# LARIX_V5_1.net
KiCad netlist of a schematic drawn in Altium Designer
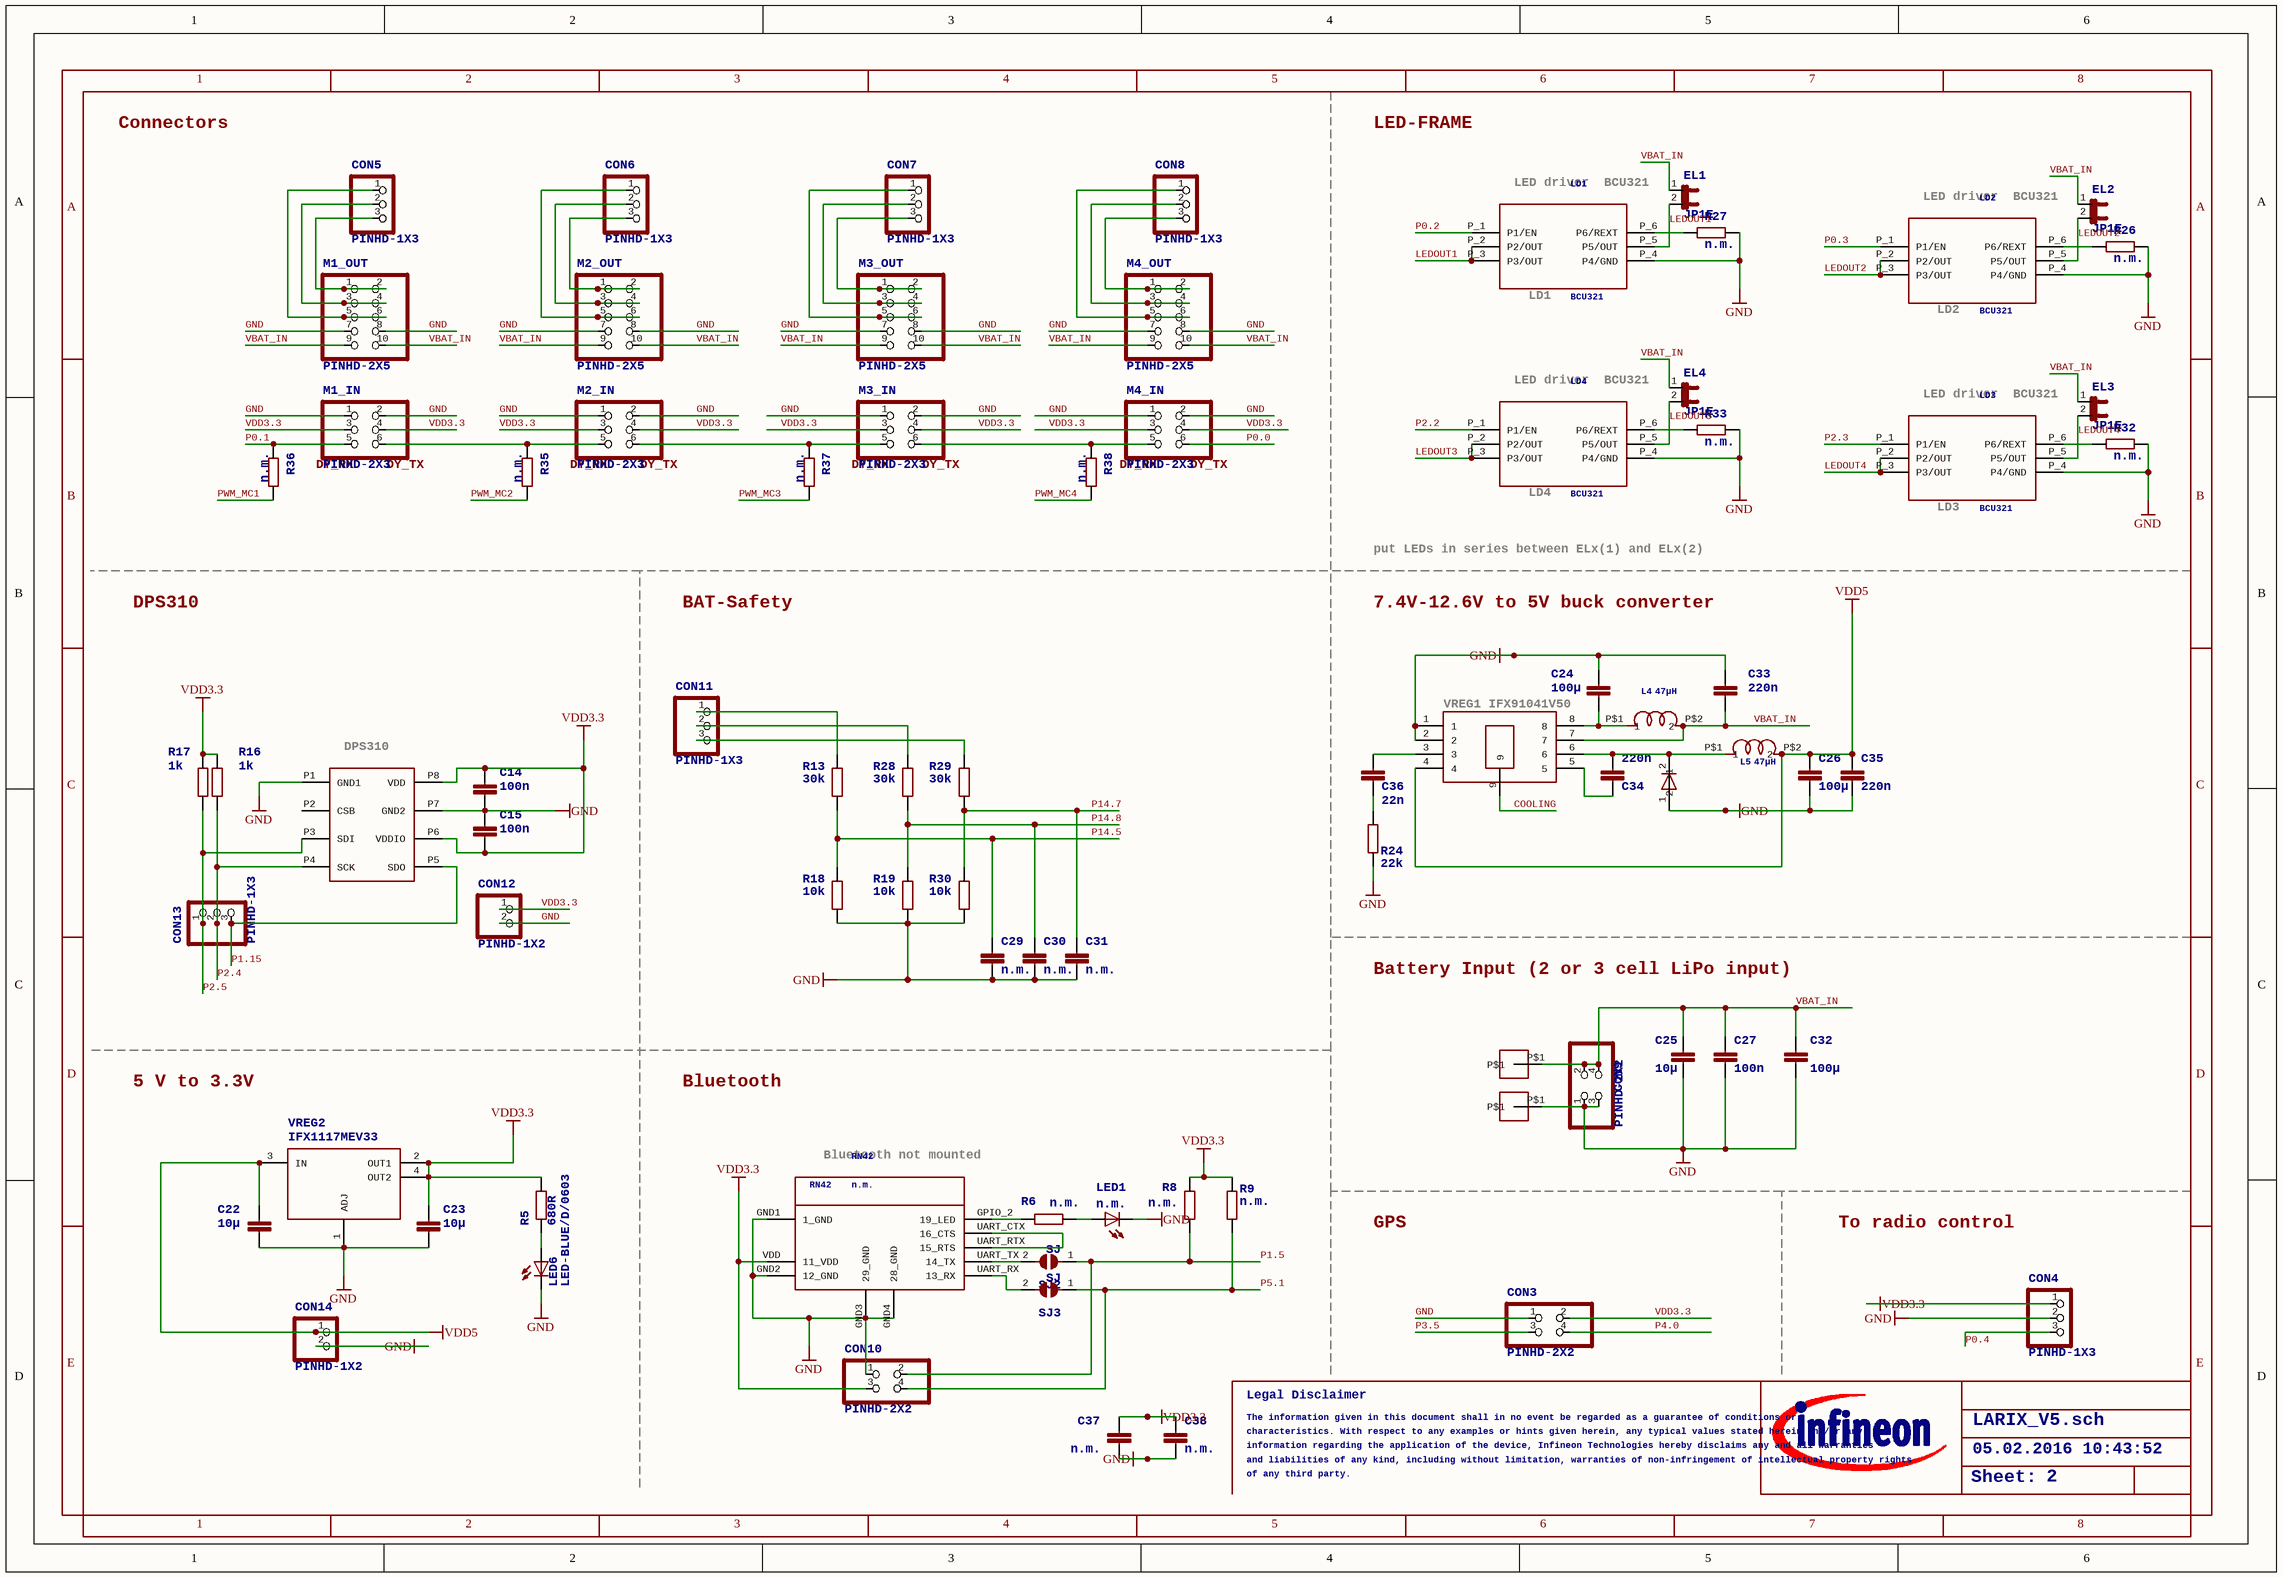
[diagram p0: LARIX_V5_1.SchDoc]

(export (version "E")
  (design (tool "Eeschema 10.0.6"))
  (components
    (comp (ref "C14")
      (value "100n")
      (footprint "C0603")
      (description "<B>CAPACITOR</B>, European symbol")
      (libsource (lib "libresistor") (part "C-EUC0603"))
    )
    (comp (ref "C15")
      (value "100n")
      (footprint "C0603")
      (description "<B>CAPACITOR</B>, European symbol")
      (libsource (lib "libresistor") (part "C-EUC0603"))
    )
    (comp (ref "C22")
      (value "10µ")
      (footprint "C0805K")
      (description "<B>CAPACITOR</B>, European symbol")
      (libsource (lib "libHMI_OLED-V1") (part "C-EUC0805K"))
    )
    (comp (ref "C23")
      (value "10µ")
      (footprint "C0805K")
      (description "<B>CAPACITOR</B>, European symbol")
      (libsource (lib "libHMI_OLED-V1") (part "C-EUC0805K"))
    )
    (comp (ref "C24")
      (value "100µ")
      (footprint "C1210")
      (description "<B>CAPACITOR</B>, European symbol")
      (libsource (lib "libresistor") (part "C-EUC1210"))
    )
    (comp (ref "C25")
      (value "10µ")
      (footprint "C0805K")
      (description "<B>CAPACITOR</B>, European symbol")
      (libsource (lib "libHMI_OLED-V1") (part "C-EUC0805K"))
    )
    (comp (ref "C26")
      (value "100µ")
      (footprint "C1210")
      (description "<B>CAPACITOR</B>, European symbol")
      (fields (field (name ">NAME") "C26") (field (name ">VALUE") "100µ"))
      (libsource (lib "libresistor") (part "C-EUC1210"))
    )
    (comp (ref "C27")
      (value "100n")
      (footprint "C0603")
      (description "<B>CAPACITOR</B>, European symbol")
      (libsource (lib "libresistor") (part "C-EUC0603"))
    )
    (comp (ref "C29")
      (value "n.m.")
      (footprint "C0603")
      (description "<B>CAPACITOR</B>, European symbol")
      (libsource (lib "libresistor") (part "C-EUC0603"))
    )
    (comp (ref "C30")
      (value "n.m.")
      (footprint "C0603")
      (description "<B>CAPACITOR</B>, European symbol")
      (libsource (lib "libresistor") (part "C-EUC0603"))
    )
    (comp (ref "C31")
      (value "n.m.")
      (footprint "C0603")
      (description "<B>CAPACITOR</B>, European symbol")
      (libsource (lib "libresistor") (part "C-EUC0603"))
    )
    (comp (ref "C32")
      (value "100µ")
      (footprint "C1210")
      (description "<B>CAPACITOR</B>, European symbol")
      (libsource (lib "libresistor") (part "C-EUC1210"))
    )
    (comp (ref "C33")
      (value "220n")
      (footprint "C0603")
      (description "<B>CAPACITOR</B>, European symbol")
      (libsource (lib "libresistor") (part "C-EUC0603"))
    )
    (comp (ref "C34")
      (value "220n")
      (footprint "C0603")
      (description "<B>CAPACITOR</B>, European symbol")
      (libsource (lib "libresistor") (part "C-EUC0603"))
    )
    (comp (ref "C35")
      (value "220n")
      (footprint "C0603")
      (description "<B>CAPACITOR</B>, European symbol")
      (libsource (lib "libresistor") (part "C-EUC0603"))
    )
    (comp (ref "C36")
      (value "22n")
      (footprint "C0603")
      (description "<B>CAPACITOR</B>, European symbol")
      (libsource (lib "libresistor") (part "C-EUC0603"))
    )
    (comp (ref "C37")
      (value "n.m.")
      (footprint "C0805K")
      (description "<B>CAPACITOR</B>, European symbol")
      (libsource (lib "libHMI_OLED-V1") (part "C-EUC0805K"))
    )
    (comp (ref "C38")
      (value "n.m.")
      (footprint "C0603")
      (description "<B>CAPACITOR</B>, European symbol")
      (libsource (lib "libresistor") (part "C-EUC0603"))
    )
    (comp (ref "CON3")
      (value "PINHD-2X2")
      (footprint "2X02")
      (description "<b>PIN HEADER</b>")
      (fields (field (name ">NAME") "CON3") (field (name ">VALUE") "PINHD-2X2"))
      (libsource (lib "pinhead") (part "PINHD-2X2"))
    )
    (comp (ref "CON4")
      (value "PINHD-1X3")
      (footprint "1X03")
      (description "<b>PIN HEADER</b>")
      (fields (field (name ">NAME") "CON4") (field (name ">VALUE") "PINHD-1X3"))
      (libsource (lib "pinhead") (part "PINHD-1X3"))
    )
    (comp (ref "CON5")
      (value "PINHD-1X3")
      (footprint "1X03")
      (description "<b>PIN HEADER</b>")
      (fields (field (name ">NAME") "CON5") (field (name ">VALUE") "PINHD-1X3"))
      (libsource (lib "pinhead") (part "PINHD-1X3"))
    )
    (comp (ref "CON6")
      (value "PINHD-1X3")
      (footprint "1X03")
      (description "<b>PIN HEADER</b>")
      (fields (field (name ">NAME") "CON6") (field (name ">VALUE") "PINHD-1X3"))
      (libsource (lib "pinhead") (part "PINHD-1X3"))
    )
    (comp (ref "CON7")
      (value "PINHD-1X3")
      (footprint "1X03")
      (description "<b>PIN HEADER</b>")
      (fields (field (name ">NAME") "CON7") (field (name ">VALUE") "PINHD-1X3"))
      (libsource (lib "pinhead") (part "PINHD-1X3"))
    )
    (comp (ref "CON8")
      (value "PINHD-1X3")
      (footprint "1X03")
      (description "<b>PIN HEADER</b>")
      (fields (field (name ">NAME") "CON8") (field (name ">VALUE") "PINHD-1X3"))
      (libsource (lib "pinhead") (part "PINHD-1X3"))
    )
    (comp (ref "CON9")
      (value "PINHD-2X2")
      (footprint "2X02")
      (description "<b>PIN HEADER</b>")
      (libsource (lib "pinhead") (part "PINHD-2X2"))
    )
    (comp (ref "CON10")
      (value "PINHD-2X2")
      (footprint "2X02")
      (description "<b>PIN HEADER</b>")
      (fields (field (name ">NAME") "CON10") (field (name ">VALUE") "PINHD-2X2"))
      (libsource (lib "pinhead") (part "PINHD-2X2"))
    )
    (comp (ref "CON11")
      (value "PINHD-1X3")
      (footprint "1X03")
      (description "<b>PIN HEADER</b>")
      (fields (field (name ">NAME") "CON11") (field (name ">VALUE") "PINHD-1X3"))
      (libsource (lib "pinhead") (part "PINHD-1X3"))
    )
    (comp (ref "CON12")
      (value "PINHD-1X2")
      (footprint "1X02")
      (description "<b>PIN HEADER</b>")
      (fields (field (name ">NAME") "CON12") (field (name ">VALUE") "PINHD-1X2"))
      (libsource (lib "pinhead") (part "PINHD-1X2"))
    )
    (comp (ref "CON13")
      (value "PINHD-1X3")
      (footprint "1X03")
      (description "<b>PIN HEADER</b>")
      (fields (field (name ">NAME") "CON13") (field (name ">VALUE") "PINHD-1X3"))
      (libsource (lib "pinhead") (part "PINHD-1X3"))
    )
    (comp (ref "CON14")
      (value "PINHD-1X2")
      (footprint "1X02")
      (description "<b>PIN HEADER</b>")
      (fields (field (name ">NAME") "CON14") (field (name ">VALUE") "PINHD-1X2"))
      (libsource (lib "pinhead") (part "PINHD-1X2"))
    )
    (comp (ref "D6")
      (value "BAS21-03W")
      (footprint "INF-SOD323_V_1PRIMARY")
      (libsource (lib "libBAS21-03W_INF-SOD323V") (part "INF-SOD323_V_1"))
    )
    (comp (ref "DPS310")
      (value "Infineon")
      (footprint "LGA8R125P0X4_500X300X120")
      (libsource (lib "libdrucksensorDPS310") (part "DPS310DRUCKSENSOR"))
    )
    (comp (ref "EL1")
      (value "JP1E")
      (footprint "JP1")
      (description "<b>JUMPER</b>")
      (fields (field (name ">NAME") "EL1") (field (name ">VALUE") "JP1E"))
      (libsource (lib "libjumper") (part "JP1E"))
    )
    (comp (ref "EL2")
      (value "JP1E")
      (footprint "JP1")
      (description "<b>JUMPER</b>")
      (fields (field (name ">NAME") "EL2") (field (name ">VALUE") "JP1E"))
      (libsource (lib "libjumper") (part "JP1E"))
    )
    (comp (ref "EL3")
      (value "JP1E")
      (footprint "JP1")
      (description "<b>JUMPER</b>")
      (fields (field (name ">NAME") "EL3") (field (name ">VALUE") "JP1E"))
      (libsource (lib "libjumper") (part "JP1E"))
    )
    (comp (ref "EL4")
      (value "JP1E")
      (footprint "JP1")
      (description "<b>JUMPER</b>")
      (fields (field (name ">NAME") "EL4") (field (name ">VALUE") "JP1E"))
      (libsource (lib "libjumper") (part "JP1E"))
    )
    (comp (ref "L4")
      (value "47µH")
      (footprint "WE-TPC")
      (libsource (lib "lib47µHWuerthChoke") (part "WUERTH47UHIND"))
    )
    (comp (ref "L5")
      (value "47µH")
      (footprint "WE-TPC")
      (libsource (lib "lib47µHWuerthChoke") (part "WUERTH47UHIND"))
    )
    (comp (ref "LD1")
      (value "BCU321")
      (footprint "SC74")
      (fields (field (name ">NAME") "LD1") (field (name ">VALUE") "BCU321"))
      (libsource (lib "libLEDtreiber BCR320U") (part "BCU320"))
    )
    (comp (ref "LD2")
      (value "BCU321")
      (footprint "SC74")
      (fields (field (name ">NAME") "LD2") (field (name ">VALUE") "BCU321"))
      (libsource (lib "libLEDtreiber BCR320U") (part "BCU320"))
    )
    (comp (ref "LD3")
      (value "BCU321")
      (footprint "SC74")
      (fields (field (name ">NAME") "LD3") (field (name ">VALUE") "BCU321"))
      (libsource (lib "libLEDtreiber BCR320U") (part "BCU320"))
    )
    (comp (ref "LD4")
      (value "BCU321")
      (footprint "SC74")
      (fields (field (name ">NAME") "LD4") (field (name ">VALUE") "BCU321"))
      (libsource (lib "libLEDtreiber BCR320U") (part "BCU320"))
    )
    (comp (ref "LED1")
      (value "n.m.")
      (footprint "CHIPLED_0603")
      (libsource (lib "libled") (part "LEDCHIPLED_0603"))
    )
    (comp (ref "LED6")
      (value "LED-BLUE/D/0603")
      (footprint "CHIPLED_0603")
      (fields (field (name ">NAME") "LED6") (field (name ">VALUE") "LED-BLUE/D/0603"))
      (libsource (lib "libled") (part "LEDCHIPLED_0603"))
    )
    (comp (ref "M1_IN")
      (value "PINHD-2X3")
      (footprint "2X03")
      (description "<b>PIN HEADER</b>")
      (fields (field (name ">NAME") "M1_IN") (field (name ">VALUE") "PINHD-2X3"))
      (libsource (lib "pinhead") (part "PINHD-2X3"))
    )
    (comp (ref "M1_OUT")
      (value "PINHD-2X5")
      (footprint "2X05")
      (description "<b>PIN HEADER</b>")
      (fields (field (name ">NAME") "M1_OUT") (field (name ">VALUE") "PINHD-2X5"))
      (libsource (lib "pinhead") (part "PINHD-2X5"))
    )
    (comp (ref "M2_IN")
      (value "PINHD-2X3")
      (footprint "2X03")
      (description "<b>PIN HEADER</b>")
      (fields (field (name ">NAME") "M2_IN") (field (name ">VALUE") "PINHD-2X3"))
      (libsource (lib "pinhead") (part "PINHD-2X3"))
    )
    (comp (ref "M2_OUT")
      (value "PINHD-2X5")
      (footprint "2X05")
      (description "<b>PIN HEADER</b>")
      (fields (field (name ">NAME") "M2_OUT") (field (name ">VALUE") "PINHD-2X5"))
      (libsource (lib "pinhead") (part "PINHD-2X5"))
    )
    (comp (ref "M3_IN")
      (value "PINHD-2X3")
      (footprint "2X03")
      (description "<b>PIN HEADER</b>")
      (fields (field (name ">NAME") "M3_IN") (field (name ">VALUE") "PINHD-2X3"))
      (libsource (lib "pinhead") (part "PINHD-2X3"))
    )
    (comp (ref "M3_OUT")
      (value "PINHD-2X5")
      (footprint "2X05")
      (description "<b>PIN HEADER</b>")
      (fields (field (name ">NAME") "M3_OUT") (field (name ">VALUE") "PINHD-2X5"))
      (libsource (lib "pinhead") (part "PINHD-2X5"))
    )
    (comp (ref "M4_IN")
      (value "PINHD-2X3")
      (footprint "2X03")
      (description "<b>PIN HEADER</b>")
      (fields (field (name ">NAME") "M4_IN") (field (name ">VALUE") "PINHD-2X3"))
      (libsource (lib "pinhead") (part "PINHD-2X3"))
    )
    (comp (ref "M4_OUT")
      (value "PINHD-2X5")
      (footprint "2X05")
      (description "<b>PIN HEADER</b>")
      (fields (field (name ">NAME") "M4_OUT") (field (name ">VALUE") "PINHD-2X5"))
      (libsource (lib "pinhead") (part "PINHD-2X5"))
    )
    (comp (ref "PAD1")
      (value "PAD-BATTERY")
      (footprint "BATT-SOLDER")
      (libsource (lib "pad_battery") (part "PAD-BATTERY"))
    )
    (comp (ref "PAD2")
      (value "PAD-BATTERY")
      (footprint "BATT-SOLDER")
      (libsource (lib "pad_battery") (part "PAD-BATTERY"))
    )
    (comp (ref "R5")
      (value "680R")
      (footprint "R0603")
      (fields (field (name ">NAME") "R5") (field (name ">VALUE") "680R"))
      (libsource (lib "libDsR") (part "R-EU_R0603"))
    )
    (comp (ref "R6") (value "n.m.") (footprint "R0603") (libsource (lib "libDsR") (part "R-EU_R0603")))
    (comp (ref "R8") (value "n.m.") (footprint "R0603") (libsource (lib "libDsR") (part "R-EU_R0603")))
    (comp (ref "R9") (value "n.m.") (footprint "R0603") (libsource (lib "libDsR") (part "R-EU_R0603")))
    (comp (ref "R13") (value "30k") (footprint "R0603") (libsource (lib "libDsR") (part "R-EU_R0603")))
    (comp (ref "R16") (value "1k") (footprint "R0603") (libsource (lib "libDsR") (part "R-EU_R0603")))
    (comp (ref "R17") (value "1k") (footprint "R0603") (libsource (lib "libDsR") (part "R-EU_R0603")))
    (comp (ref "R18") (value "10k") (footprint "R0603") (libsource (lib "libDsR") (part "R-EU_R0603")))
    (comp (ref "R19") (value "10k") (footprint "R0603") (libsource (lib "libDsR") (part "R-EU_R0603")))
    (comp (ref "R24") (value "22k") (footprint "R0603") (libsource (lib "libDsR") (part "R-EU_R0603")))
    (comp (ref "R26")
      (value "n.m.")
      (footprint "R0603")
      (description "<B>RESISTOR</B>, European symbol")
      (libsource (lib "libresistor") (part "R-EU_R0603"))
    )
    (comp (ref "R27")
      (value "n.m.")
      (footprint "R0603")
      (description "<B>RESISTOR</B>, European symbol")
      (libsource (lib "libresistor") (part "R-EU_R0603"))
    )
    (comp (ref "R28") (value "30k") (footprint "R0603") (libsource (lib "libDsR") (part "R-EU_R0603")))
    (comp (ref "R29") (value "30k") (footprint "R0603") (libsource (lib "libDsR") (part "R-EU_R0603")))
    (comp (ref "R30") (value "10k") (footprint "R0603") (libsource (lib "libDsR") (part "R-EU_R0603")))
    (comp (ref "R32")
      (value "n.m.")
      (footprint "R0603")
      (description "<B>RESISTOR</B>, European symbol")
      (libsource (lib "libresistor") (part "R-EU_R0603"))
    )
    (comp (ref "R33")
      (value "n.m.")
      (footprint "R0603")
      (description "<B>RESISTOR</B>, European symbol")
      (libsource (lib "libresistor") (part "R-EU_R0603"))
    )
    (comp (ref "R35")
      (value "n.m.")
      (footprint "R0603")
      (description "<B>RESISTOR</B>, European symbol")
      (fields (field (name ">NAME") "R35") (field (name ">VALUE") "n.m."))
      (libsource (lib "libresistor") (part "R-EU_R0603"))
    )
    (comp (ref "R36")
      (value "n.m.")
      (footprint "R0603")
      (description "<B>RESISTOR</B>, European symbol")
      (fields (field (name ">NAME") "R36") (field (name ">VALUE") "n.m."))
      (libsource (lib "libresistor") (part "R-EU_R0603"))
    )
    (comp (ref "R37")
      (value "n.m.")
      (footprint "R0603")
      (fields (field (name ">NAME") "R37") (field (name ">VALUE") "n.m."))
      (libsource (lib "libDsR") (part "R-EU_R0603"))
    )
    (comp (ref "R38")
      (value "n.m.")
      (footprint "R0603")
      (description "<B>RESISTOR</B>, European symbol")
      (fields (field (name ">NAME") "R38") (field (name ">VALUE") "n.m."))
      (libsource (lib "libresistor") (part "R-EU_R0603"))
    )
    (comp (ref "RN42")
      (value "n.m.")
      (footprint "RN42+SHIELD")
      (fields (field (name "RN42") "RN42") (field (name ">NAME") "RN42") (field (name ">VALUE") "n.m."))
      (libsource (lib "libbluetoothRN42") (part "BLUETOOTHRN42+SHIELD"))
    )
    (comp (ref "SJ2")
      (value "SJ")
      (footprint "SJ")
      (description "SMD solder <b>JUMPER</b>")
      (fields (field (name ">NAME") "SJ2") (field (name ">VALUE") "SJ"))
      (libsource (lib "jumper") (part "SJ"))
    )
    (comp (ref "SJ3")
      (value "SJ")
      (footprint "SJ")
      (description "SMD solder <b>JUMPER</b>")
      (fields (field (name ">NAME") "SJ3") (field (name ">VALUE") "SJ"))
      (libsource (lib "jumper") (part "SJ"))
    )
    (comp (ref "VREG1")
      (value "IFX91041V50")
      (footprint "INF-PG-DSO-8-27_N_1PRIMARY")
      (libsource (lib "libInfineon-DCDC-91041 - DSO-8") (part "INF-PG-DSO-8-27_N_1"))
    )
    (comp (ref "VREG2")
      (value "IFX1117MEV33")
      (footprint "SOT223")
      (fields (field (name ">NAME") "VREG2") (field (name ">VALUE") "IFX1117MEV33"))
      (libsource (lib "libXMC4500_Relax-V1+USBvertical") (part "IFX1117"))
    )
  )
  (nets
    (net (code "1") (name "/COOLING") (class "Default")
      (node (ref "VREG1") (pin "9") (pinfunction "9_9") (pintype "passive"))
    )
    (net (code "2") (name "/LEDOUT1") (class "Default")
      (node (ref "EL1") (pin "2") (pinfunction "2_2") (pintype "passive"))
      (node (ref "LD1") (pin "P_2") (pinfunction "P2/OUT_P_2") (pintype "passive"))
      (node (ref "LD1") (pin "P_3") (pinfunction "P3/OUT_P_3") (pintype "passive"))
      (node (ref "LD1") (pin "P_5") (pinfunction "P5/OUT_P_5") (pintype "passive"))
    )
    (net (code "3") (name "/LEDOUT2") (class "Default")
      (node (ref "EL2") (pin "2") (pinfunction "2_2") (pintype "passive"))
      (node (ref "LD2") (pin "P_2") (pinfunction "P2/OUT_P_2") (pintype "passive"))
      (node (ref "LD2") (pin "P_3") (pinfunction "P3/OUT_P_3") (pintype "passive"))
      (node (ref "LD2") (pin "P_5") (pinfunction "P5/OUT_P_5") (pintype "passive"))
    )
    (net (code "4") (name "/LEDOUT3") (class "Default")
      (node (ref "EL4") (pin "2") (pinfunction "2_2") (pintype "passive"))
      (node (ref "LD4") (pin "P_2") (pinfunction "P2/OUT_P_2") (pintype "passive"))
      (node (ref "LD4") (pin "P_3") (pinfunction "P3/OUT_P_3") (pintype "passive"))
      (node (ref "LD4") (pin "P_5") (pinfunction "P5/OUT_P_5") (pintype "passive"))
    )
    (net (code "5") (name "/LEDOUT4") (class "Default")
      (node (ref "EL3") (pin "2") (pinfunction "2_2") (pintype "passive"))
      (node (ref "LD3") (pin "P_2") (pinfunction "P2/OUT_P_2") (pintype "passive"))
      (node (ref "LD3") (pin "P_3") (pinfunction "P3/OUT_P_3") (pintype "passive"))
      (node (ref "LD3") (pin "P_5") (pinfunction "P5/OUT_P_5") (pintype "passive"))
    )
    (net (code "6") (name "/P0.0") (class "Default")
      (node (ref "M4_IN") (pin "6") (pinfunction "6_6") (pintype "passive"))
    )
    (net (code "7") (name "/P0.1") (class "Default")
      (node (ref "M1_IN") (pin "5") (pinfunction "5_5") (pintype "passive"))
      (node (ref "R36") (pin "1") (pinfunction "1_1") (pintype "passive"))
    )
    (net (code "8") (name "/P0.2") (class "Default")
      (node (ref "LD1") (pin "P_1") (pinfunction "P1/EN_P_1") (pintype "passive"))
    )
    (net (code "9") (name "/P0.3") (class "Default")
      (node (ref "LD2") (pin "P_1") (pinfunction "P1/EN_P_1") (pintype "passive"))
    )
    (net (code "10") (name "/P0.4") (class "Default")
      (node (ref "CON4") (pin "3") (pinfunction "3_3") (pintype "passive"))
    )
    (net (code "11") (name "/P1.5") (class "Default")
      (node (ref "CON10") (pin "2") (pinfunction "2_2") (pintype "passive"))
      (node (ref "R8") (pin "2") (pinfunction "2_2") (pintype "passive"))
      (node (ref "SJ2") (pin "1") (pinfunction "1_1") (pintype "passive"))
    )
    (net (code "12") (name "/P1.15") (class "Default")
      (node (ref "CON13") (pin "3") (pinfunction "3_3") (pintype "passive"))
      (node (ref "DPS310") (pin "P5") (pinfunction "SDO_P5") (pintype "passive"))
    )
    (net (code "13") (name "/P2.2") (class "Default")
      (node (ref "LD4") (pin "P_1") (pinfunction "P1/EN_P_1") (pintype "passive"))
    )
    (net (code "14") (name "/P2.3") (class "Default")
      (node (ref "LD3") (pin "P_1") (pinfunction "P1/EN_P_1") (pintype "passive"))
    )
    (net (code "15") (name "/P2.4") (class "Default")
      (node (ref "CON13") (pin "2") (pinfunction "2_2") (pintype "passive"))
      (node (ref "DPS310") (pin "P4") (pinfunction "SCK_P4") (pintype "passive"))
      (node (ref "R16") (pin "2") (pinfunction "2_2") (pintype "passive"))
    )
    (net (code "16") (name "/P2.5") (class "Default")
      (node (ref "CON13") (pin "1") (pinfunction "1_1") (pintype "passive"))
      (node (ref "DPS310") (pin "P3") (pinfunction "SDI_P3") (pintype "passive"))
      (node (ref "R17") (pin "2") (pinfunction "2_2") (pintype "passive"))
    )
    (net (code "17") (name "/P3.5") (class "Default")
      (node (ref "CON3") (pin "3") (pinfunction "3_3") (pintype "passive"))
    )
    (net (code "18") (name "/P4.0") (class "Default")
      (node (ref "CON3") (pin "4") (pinfunction "4_4") (pintype "passive"))
    )
    (net (code "19") (name "/P5.1") (class "Default")
      (node (ref "CON10") (pin "4") (pinfunction "4_4") (pintype "passive"))
      (node (ref "R9") (pin "2") (pinfunction "2_2") (pintype "passive"))
      (node (ref "SJ3") (pin "1") (pinfunction "1_1") (pintype "passive"))
    )
    (net (code "20") (name "/P14.5") (class "Default")
      (node (ref "C29") (pin "1") (pinfunction "1_1") (pintype "passive"))
      (node (ref "R13") (pin "2") (pinfunction "2_2") (pintype "passive"))
      (node (ref "R18") (pin "1") (pinfunction "1_1") (pintype "passive"))
    )
    (net (code "21") (name "/P14.7") (class "Default")
      (node (ref "C31") (pin "1") (pinfunction "1_1") (pintype "passive"))
      (node (ref "R29") (pin "2") (pinfunction "2_2") (pintype "passive"))
      (node (ref "R30") (pin "1") (pinfunction "1_1") (pintype "passive"))
    )
    (net (code "22") (name "/P14.8") (class "Default")
      (node (ref "C30") (pin "1") (pinfunction "1_1") (pintype "passive"))
      (node (ref "R19") (pin "1") (pinfunction "1_1") (pintype "passive"))
      (node (ref "R28") (pin "2") (pinfunction "2_2") (pintype "passive"))
    )
    (net (code "23") (name "/PWM_MC1") (class "Default")
      (node (ref "R36") (pin "2") (pinfunction "2_2") (pintype "passive"))
    )
    (net (code "24") (name "/PWM_MC2") (class "Default")
      (node (ref "R35") (pin "2") (pinfunction "2_2") (pintype "passive"))
    )
    (net (code "25") (name "/PWM_MC3") (class "Default")
      (node (ref "R37") (pin "2") (pinfunction "2_2") (pintype "passive"))
    )
    (net (code "26") (name "/PWM_MC4") (class "Default")
      (node (ref "R38") (pin "2") (pinfunction "2_2") (pintype "passive"))
    )
    (net (code "27") (name "/VBAT_IN") (class "Default")
      (node (ref "C25") (pin "1") (pinfunction "1_1") (pintype "passive"))
      (node (ref "C27") (pin "1") (pinfunction "1_1") (pintype "passive"))
      (node (ref "C32") (pin "1") (pinfunction "1_1") (pintype "passive"))
      (node (ref "C33") (pin "2") (pinfunction "2_2") (pintype "passive"))
      (node (ref "CON9") (pin "2") (pinfunction "2_2") (pintype "passive"))
      (node (ref "CON9") (pin "4") (pinfunction "4_4") (pintype "passive"))
      (node (ref "EL1") (pin "1") (pinfunction "1_1") (pintype "passive"))
      (node (ref "EL2") (pin "1") (pinfunction "1_1") (pintype "passive"))
      (node (ref "EL3") (pin "1") (pinfunction "1_1") (pintype "passive"))
      (node (ref "EL4") (pin "1") (pinfunction "1_1") (pintype "passive"))
      (node (ref "L4") (pin "P$2") (pinfunction "2_P$2") (pintype "passive"))
      (node (ref "M1_OUT") (pin "10") (pinfunction "10_10") (pintype "passive"))
      (node (ref "M1_OUT") (pin "9") (pinfunction "9_9") (pintype "passive"))
      (node (ref "M2_OUT") (pin "10") (pinfunction "10_10") (pintype "passive"))
      (node (ref "M2_OUT") (pin "9") (pinfunction "9_9") (pintype "passive"))
      (node (ref "M3_OUT") (pin "10") (pinfunction "10_10") (pintype "passive"))
      (node (ref "M3_OUT") (pin "9") (pinfunction "9_9") (pintype "passive"))
      (node (ref "M4_OUT") (pin "10") (pinfunction "10_10") (pintype "passive"))
      (node (ref "M4_OUT") (pin "9") (pinfunction "9_9") (pintype "passive"))
      (node (ref "PAD1") (pin "P$1") (pinfunction "P$1_P$1") (pintype "passive"))
      (node (ref "VREG1") (pin "7") (pinfunction "7_7") (pintype "passive"))
    )
    (net (code "28") (name "GND") (class "Default")
      (node (ref "C14") (pin "2") (pinfunction "2_2") (pintype "passive"))
      (node (ref "C15") (pin "1") (pinfunction "1_1") (pintype "passive"))
      (node (ref "C22") (pin "2") (pinfunction "2_2") (pintype "passive"))
      (node (ref "C23") (pin "2") (pinfunction "2_2") (pintype "passive"))
      (node (ref "C24") (pin "1") (pinfunction "1_1") (pintype "passive"))
      (node (ref "C25") (pin "2") (pinfunction "2_2") (pintype "passive"))
      (node (ref "C26") (pin "2") (pinfunction "2_2") (pintype "passive"))
      (node (ref "C27") (pin "2") (pinfunction "2_2") (pintype "passive"))
      (node (ref "C29") (pin "2") (pinfunction "2_2") (pintype "passive"))
      (node (ref "C30") (pin "2") (pinfunction "2_2") (pintype "passive"))
      (node (ref "C31") (pin "2") (pinfunction "2_2") (pintype "passive"))
      (node (ref "C32") (pin "2") (pinfunction "2_2") (pintype "passive"))
      (node (ref "C33") (pin "1") (pinfunction "1_1") (pintype "passive"))
      (node (ref "C35") (pin "2") (pinfunction "2_2") (pintype "passive"))
      (node (ref "C37") (pin "2") (pinfunction "2_2") (pintype "passive"))
      (node (ref "C38") (pin "2") (pinfunction "2_2") (pintype "passive"))
      (node (ref "CON10") (pin "1") (pinfunction "1_1") (pintype "passive"))
      (node (ref "CON12") (pin "2") (pinfunction "2_2") (pintype "passive"))
      (node (ref "CON14") (pin "2") (pinfunction "2_2") (pintype "passive"))
      (node (ref "CON3") (pin "1") (pinfunction "1_1") (pintype "passive"))
      (node (ref "CON4") (pin "2") (pinfunction "2_2") (pintype "passive"))
      (node (ref "CON9") (pin "1") (pinfunction "1_1") (pintype "passive"))
      (node (ref "CON9") (pin "3") (pinfunction "3_3") (pintype "passive"))
      (node (ref "D6") (pin "1") (pinfunction "1_1") (pintype "passive"))
      (node (ref "DPS310") (pin "P1") (pinfunction "GND1_P1") (pintype "passive"))
      (node (ref "DPS310") (pin "P7") (pinfunction "GND2_P7") (pintype "passive"))
      (node (ref "LD1") (pin "P_4") (pinfunction "P4/GND_P_4") (pintype "passive"))
      (node (ref "LD2") (pin "P_4") (pinfunction "P4/GND_P_4") (pintype "passive"))
      (node (ref "LD3") (pin "P_4") (pinfunction "P4/GND_P_4") (pintype "passive"))
      (node (ref "LD4") (pin "P_4") (pinfunction "P4/GND_P_4") (pintype "passive"))
      (node (ref "LED1") (pin "C") (pinfunction "C_C") (pintype "passive"))
      (node (ref "LED6") (pin "C") (pinfunction "C_C") (pintype "passive"))
      (node (ref "M1_IN") (pin "1") (pinfunction "1_1") (pintype "passive"))
      (node (ref "M1_IN") (pin "2") (pinfunction "2_2") (pintype "passive"))
      (node (ref "M1_OUT") (pin "7") (pinfunction "7_7") (pintype "passive"))
      (node (ref "M1_OUT") (pin "8") (pinfunction "8_8") (pintype "passive"))
      (node (ref "M2_IN") (pin "1") (pinfunction "1_1") (pintype "passive"))
      (node (ref "M2_IN") (pin "2") (pinfunction "2_2") (pintype "passive"))
      (node (ref "M2_OUT") (pin "7") (pinfunction "7_7") (pintype "passive"))
      (node (ref "M2_OUT") (pin "8") (pinfunction "8_8") (pintype "passive"))
      (node (ref "M3_IN") (pin "1") (pinfunction "1_1") (pintype "passive"))
      (node (ref "M3_IN") (pin "2") (pinfunction "2_2") (pintype "passive"))
      (node (ref "M3_OUT") (pin "7") (pinfunction "7_7") (pintype "passive"))
      (node (ref "M3_OUT") (pin "8") (pinfunction "8_8") (pintype "passive"))
      (node (ref "M4_IN") (pin "1") (pinfunction "1_1") (pintype "passive"))
      (node (ref "M4_IN") (pin "2") (pinfunction "2_2") (pintype "passive"))
      (node (ref "M4_OUT") (pin "7") (pinfunction "7_7") (pintype "passive"))
      (node (ref "M4_OUT") (pin "8") (pinfunction "8_8") (pintype "passive"))
      (node (ref "PAD2") (pin "P$1") (pinfunction "P$1_P$1") (pintype "passive"))
      (node (ref "R18") (pin "2") (pinfunction "2_2") (pintype "passive"))
      (node (ref "R19") (pin "2") (pinfunction "2_2") (pintype "passive"))
      (node (ref "R24") (pin "2") (pinfunction "2_2") (pintype "passive"))
      (node (ref "R26") (pin "2") (pinfunction "2_2") (pintype "passive"))
      (node (ref "R27") (pin "2") (pinfunction "2_2") (pintype "passive"))
      (node (ref "R30") (pin "2") (pinfunction "2_2") (pintype "passive"))
      (node (ref "R32") (pin "2") (pinfunction "2_2") (pintype "passive"))
      (node (ref "R33") (pin "2") (pinfunction "2_2") (pintype "passive"))
      (node (ref "RN42") (pin "GND1") (pinfunction "1_GND_GND1") (pintype "passive"))
      (node (ref "RN42") (pin "GND2") (pinfunction "12_GND_GND2") (pintype "passive"))
      (node (ref "RN42") (pin "GND3") (pinfunction "29_GND_GND3") (pintype "passive"))
      (node (ref "RN42") (pin "GND4") (pinfunction "28_GND_GND4") (pintype "passive"))
      (node (ref "VREG1") (pin "1") (pinfunction "1_1") (pintype "passive"))
      (node (ref "VREG1") (pin "2") (pinfunction "2_2") (pintype "passive"))
      (node (ref "VREG2") (pin "1") (pinfunction "ADJ_1") (pintype "power_in"))
    )
    (net (code "29") (name "Net-(C34-Pad2)") (class "Default")
      (node (ref "C34") (pin "2") (pinfunction "2_2") (pintype "passive"))
      (node (ref "VREG1") (pin "5") (pinfunction "5_5") (pintype "passive"))
    )
    (net (code "30") (name "Net-(C36-Pad1)") (class "Default")
      (node (ref "C36") (pin "1") (pinfunction "1_1") (pintype "passive"))
      (node (ref "VREG1") (pin "3") (pinfunction "3_3") (pintype "passive"))
    )
    (net (code "31") (name "Net-(C36-Pad2)") (class "Default")
      (node (ref "C36") (pin "2") (pinfunction "2_2") (pintype "passive"))
      (node (ref "R24") (pin "1") (pinfunction "1_1") (pintype "passive"))
    )
    (net (code "32") (name "Net-(CON5-Pad1)") (class "Default")
      (node (ref "CON5") (pin "1") (pinfunction "1_1") (pintype "passive"))
      (node (ref "M1_OUT") (pin "5") (pinfunction "5_5") (pintype "passive"))
      (node (ref "M1_OUT") (pin "6") (pinfunction "6_6") (pintype "passive"))
    )
    (net (code "33") (name "Net-(CON5-Pad2)") (class "Default")
      (node (ref "CON5") (pin "2") (pinfunction "2_2") (pintype "passive"))
      (node (ref "M1_OUT") (pin "3") (pinfunction "3_3") (pintype "passive"))
      (node (ref "M1_OUT") (pin "4") (pinfunction "4_4") (pintype "passive"))
    )
    (net (code "34") (name "Net-(CON5-Pad3)") (class "Default")
      (node (ref "CON5") (pin "3") (pinfunction "3_3") (pintype "passive"))
      (node (ref "M1_OUT") (pin "1") (pinfunction "1_1") (pintype "passive"))
      (node (ref "M1_OUT") (pin "2") (pinfunction "2_2") (pintype "passive"))
    )
    (net (code "35") (name "Net-(CON6-Pad1)") (class "Default")
      (node (ref "CON6") (pin "1") (pinfunction "1_1") (pintype "passive"))
      (node (ref "M2_OUT") (pin "5") (pinfunction "5_5") (pintype "passive"))
      (node (ref "M2_OUT") (pin "6") (pinfunction "6_6") (pintype "passive"))
    )
    (net (code "36") (name "Net-(CON6-Pad2)") (class "Default")
      (node (ref "CON6") (pin "2") (pinfunction "2_2") (pintype "passive"))
      (node (ref "M2_OUT") (pin "3") (pinfunction "3_3") (pintype "passive"))
      (node (ref "M2_OUT") (pin "4") (pinfunction "4_4") (pintype "passive"))
    )
    (net (code "37") (name "Net-(CON6-Pad3)") (class "Default")
      (node (ref "CON6") (pin "3") (pinfunction "3_3") (pintype "passive"))
      (node (ref "M2_OUT") (pin "1") (pinfunction "1_1") (pintype "passive"))
      (node (ref "M2_OUT") (pin "2") (pinfunction "2_2") (pintype "passive"))
    )
    (net (code "38") (name "Net-(CON7-Pad1)") (class "Default")
      (node (ref "CON7") (pin "1") (pinfunction "1_1") (pintype "passive"))
      (node (ref "M3_OUT") (pin "5") (pinfunction "5_5") (pintype "passive"))
      (node (ref "M3_OUT") (pin "6") (pinfunction "6_6") (pintype "passive"))
    )
    (net (code "39") (name "Net-(CON7-Pad2)") (class "Default")
      (node (ref "CON7") (pin "2") (pinfunction "2_2") (pintype "passive"))
      (node (ref "M3_OUT") (pin "3") (pinfunction "3_3") (pintype "passive"))
      (node (ref "M3_OUT") (pin "4") (pinfunction "4_4") (pintype "passive"))
    )
    (net (code "40") (name "Net-(CON7-Pad3)") (class "Default")
      (node (ref "CON7") (pin "3") (pinfunction "3_3") (pintype "passive"))
      (node (ref "M3_OUT") (pin "1") (pinfunction "1_1") (pintype "passive"))
      (node (ref "M3_OUT") (pin "2") (pinfunction "2_2") (pintype "passive"))
    )
    (net (code "41") (name "Net-(CON8-Pad1)") (class "Default")
      (node (ref "CON8") (pin "1") (pinfunction "1_1") (pintype "passive"))
      (node (ref "M4_OUT") (pin "5") (pinfunction "5_5") (pintype "passive"))
      (node (ref "M4_OUT") (pin "6") (pinfunction "6_6") (pintype "passive"))
    )
    (net (code "42") (name "Net-(CON8-Pad2)") (class "Default")
      (node (ref "CON8") (pin "2") (pinfunction "2_2") (pintype "passive"))
      (node (ref "M4_OUT") (pin "3") (pinfunction "3_3") (pintype "passive"))
      (node (ref "M4_OUT") (pin "4") (pinfunction "4_4") (pintype "passive"))
    )
    (net (code "43") (name "Net-(CON8-Pad3)") (class "Default")
      (node (ref "CON8") (pin "3") (pinfunction "3_3") (pintype "passive"))
      (node (ref "M4_OUT") (pin "1") (pinfunction "1_1") (pintype "passive"))
      (node (ref "M4_OUT") (pin "2") (pinfunction "2_2") (pintype "passive"))
    )
    (net (code "44") (name "Net-(CON11-Pad1)") (class "Default")
      (node (ref "CON11") (pin "1") (pinfunction "1_1") (pintype "passive"))
      (node (ref "R13") (pin "1") (pinfunction "1_1") (pintype "passive"))
    )
    (net (code "45") (name "Net-(CON11-Pad2)") (class "Default")
      (node (ref "CON11") (pin "2") (pinfunction "2_2") (pintype "passive"))
      (node (ref "R28") (pin "1") (pinfunction "1_1") (pintype "passive"))
    )
    (net (code "46") (name "Net-(CON11-Pad3)") (class "Default")
      (node (ref "CON11") (pin "3") (pinfunction "3_3") (pintype "passive"))
      (node (ref "R29") (pin "1") (pinfunction "1_1") (pintype "passive"))
    )
    (net (code "47") (name "Net-(L4-1)") (class "Default")
      (node (ref "C24") (pin "2") (pinfunction "2_2") (pintype "passive"))
      (node (ref "L4") (pin "P$1") (pinfunction "1_P$1") (pintype "passive"))
      (node (ref "VREG1") (pin "8") (pinfunction "8_8") (pintype "passive"))
    )
    (net (code "48") (name "Net-(L5-1)") (class "Default")
      (node (ref "C34") (pin "1") (pinfunction "1_1") (pintype "passive"))
      (node (ref "D6") (pin "2") (pinfunction "2_2") (pintype "passive"))
      (node (ref "L5") (pin "P$1") (pinfunction "1_P$1") (pintype "passive"))
      (node (ref "VREG1") (pin "6") (pinfunction "6_6") (pintype "passive"))
    )
    (net (code "49") (name "Net-(LD1-P6{slash}REXT)") (class "Default")
      (node (ref "LD1") (pin "P_6") (pinfunction "P6/REXT_P_6") (pintype "passive"))
      (node (ref "R27") (pin "1") (pinfunction "1_1") (pintype "passive"))
    )
    (net (code "50") (name "Net-(LD2-P6{slash}REXT)") (class "Default")
      (node (ref "LD2") (pin "P_6") (pinfunction "P6/REXT_P_6") (pintype "passive"))
      (node (ref "R26") (pin "1") (pinfunction "1_1") (pintype "passive"))
    )
    (net (code "51") (name "Net-(LD3-P6{slash}REXT)") (class "Default")
      (node (ref "LD3") (pin "P_6") (pinfunction "P6/REXT_P_6") (pintype "passive"))
      (node (ref "R32") (pin "1") (pinfunction "1_1") (pintype "passive"))
    )
    (net (code "52") (name "Net-(LD4-P6{slash}REXT)") (class "Default")
      (node (ref "LD4") (pin "P_6") (pinfunction "P6/REXT_P_6") (pintype "passive"))
      (node (ref "R33") (pin "1") (pinfunction "1_1") (pintype "passive"))
    )
    (net (code "53") (name "Net-(LED1-PadA)") (class "Default")
      (node (ref "LED1") (pin "A") (pinfunction "A_A") (pintype "passive"))
      (node (ref "R6") (pin "1") (pinfunction "1_1") (pintype "passive"))
    )
    (net (code "54") (name "Net-(LED6-PadA)") (class "Default")
      (node (ref "LED6") (pin "A") (pinfunction "A_A") (pintype "passive"))
      (node (ref "R5") (pin "1") (pinfunction "1_1") (pintype "passive"))
    )
    (net (code "55") (name "Net-(M1_IN-Pad6)") (class "Default")
      (node (ref "M1_IN") (pin "6") (pinfunction "6_6") (pintype "passive"))
      (node (ref "M2_IN") (pin "5") (pinfunction "5_5") (pintype "passive"))
      (node (ref "R35") (pin "1") (pinfunction "1_1") (pintype "passive"))
    )
    (net (code "56") (name "Net-(M2_IN-Pad6)") (class "Default")
      (node (ref "M2_IN") (pin "6") (pinfunction "6_6") (pintype "passive"))
      (node (ref "M3_IN") (pin "5") (pinfunction "5_5") (pintype "passive"))
      (node (ref "R37") (pin "1") (pinfunction "1_1") (pintype "passive"))
    )
    (net (code "57") (name "Net-(M3_IN-Pad6)") (class "Default")
      (node (ref "M3_IN") (pin "6") (pinfunction "6_6") (pintype "passive"))
      (node (ref "M4_IN") (pin "5") (pinfunction "5_5") (pintype "passive"))
      (node (ref "R38") (pin "1") (pinfunction "1_1") (pintype "passive"))
    )
    (net (code "58") (name "Net-(RN42-13_RX)") (class "Default")
      (node (ref "RN42") (pin "UART_RX") (pinfunction "13_RX_UART_RX") (pintype "passive"))
      (node (ref "SJ3") (pin "2") (pinfunction "2_2") (pintype "passive"))
    )
    (net (code "59") (name "Net-(RN42-14_TX)") (class "Default")
      (node (ref "RN42") (pin "UART_TX") (pinfunction "14_TX_UART_TX") (pintype "passive"))
      (node (ref "SJ2") (pin "2") (pinfunction "2_2") (pintype "passive"))
    )
    (net (code "60") (name "Net-(RN42-15_RTS)") (class "Default")
      (node (ref "RN42") (pin "UART_CTX") (pinfunction "16_CTS_UART_CTX") (pintype "passive"))
      (node (ref "RN42") (pin "UART_RTX") (pinfunction "15_RTS_UART_RTX") (pintype "passive"))
    )
    (net (code "61") (name "Net-(RN42-19_LED)") (class "Default")
      (node (ref "R6") (pin "2") (pinfunction "2_2") (pintype "passive"))
      (node (ref "RN42") (pin "GPIO_2") (pinfunction "19_LED_GPIO_2") (pintype "passive"))
    )
    (net (code "62") (name "VDD3.3") (class "Default")
      (node (ref "C14") (pin "1") (pinfunction "1_1") (pintype "passive"))
      (node (ref "C15") (pin "2") (pinfunction "2_2") (pintype "passive"))
      (node (ref "C23") (pin "1") (pinfunction "1_1") (pintype "passive"))
      (node (ref "C37") (pin "1") (pinfunction "1_1") (pintype "passive"))
      (node (ref "C38") (pin "1") (pinfunction "1_1") (pintype "passive"))
      (node (ref "CON10") (pin "3") (pinfunction "3_3") (pintype "passive"))
      (node (ref "CON12") (pin "1") (pinfunction "1_1") (pintype "passive"))
      (node (ref "CON3") (pin "2") (pinfunction "2_2") (pintype "passive"))
      (node (ref "CON4") (pin "1") (pinfunction "1_1") (pintype "passive"))
      (node (ref "DPS310") (pin "P6") (pinfunction "VDDIO_P6") (pintype "passive"))
      (node (ref "DPS310") (pin "P8") (pinfunction "VDD_P8") (pintype "passive"))
      (node (ref "M1_IN") (pin "3") (pinfunction "3_3") (pintype "passive"))
      (node (ref "M1_IN") (pin "4") (pinfunction "4_4") (pintype "passive"))
      (node (ref "M2_IN") (pin "3") (pinfunction "3_3") (pintype "passive"))
      (node (ref "M2_IN") (pin "4") (pinfunction "4_4") (pintype "passive"))
      (node (ref "M3_IN") (pin "3") (pinfunction "3_3") (pintype "passive"))
      (node (ref "M3_IN") (pin "4") (pinfunction "4_4") (pintype "passive"))
      (node (ref "M4_IN") (pin "3") (pinfunction "3_3") (pintype "passive"))
      (node (ref "M4_IN") (pin "4") (pinfunction "4_4") (pintype "passive"))
      (node (ref "R16") (pin "1") (pinfunction "1_1") (pintype "passive"))
      (node (ref "R17") (pin "1") (pinfunction "1_1") (pintype "passive"))
      (node (ref "R5") (pin "2") (pinfunction "2_2") (pintype "passive"))
      (node (ref "R8") (pin "1") (pinfunction "1_1") (pintype "passive"))
      (node (ref "R9") (pin "1") (pinfunction "1_1") (pintype "passive"))
      (node (ref "RN42") (pin "VDD") (pinfunction "11_VDD_VDD") (pintype "passive"))
      (node (ref "VREG2") (pin "2") (pinfunction "OUT1_2") (pintype "power_in"))
      (node (ref "VREG2") (pin "4") (pinfunction "OUT2_4") (pintype "power_in"))
    )
    (net (code "63") (name "VDD5") (class "Default")
      (node (ref "C22") (pin "1") (pinfunction "1_1") (pintype "passive"))
      (node (ref "C26") (pin "1") (pinfunction "1_1") (pintype "passive"))
      (node (ref "C35") (pin "1") (pinfunction "1_1") (pintype "passive"))
      (node (ref "CON14") (pin "1") (pinfunction "1_1") (pintype "passive"))
      (node (ref "L5") (pin "P$2") (pinfunction "2_P$2") (pintype "passive"))
      (node (ref "VREG1") (pin "4") (pinfunction "4_4") (pintype "passive"))
      (node (ref "VREG2") (pin "3") (pinfunction "IN_3") (pintype "power_in"))
    )
    (net (code "64") (name "unconnected-(DPS310-CSB-PadP2)") (class "Default")
      (node (ref "DPS310") (pin "P2") (pinfunction "CSB_P2") (pintype "passive"))
    )
  )
)
